# 02_ESP12_CORE.net
KiCad netlist of a schematic drawn in Altium Designer
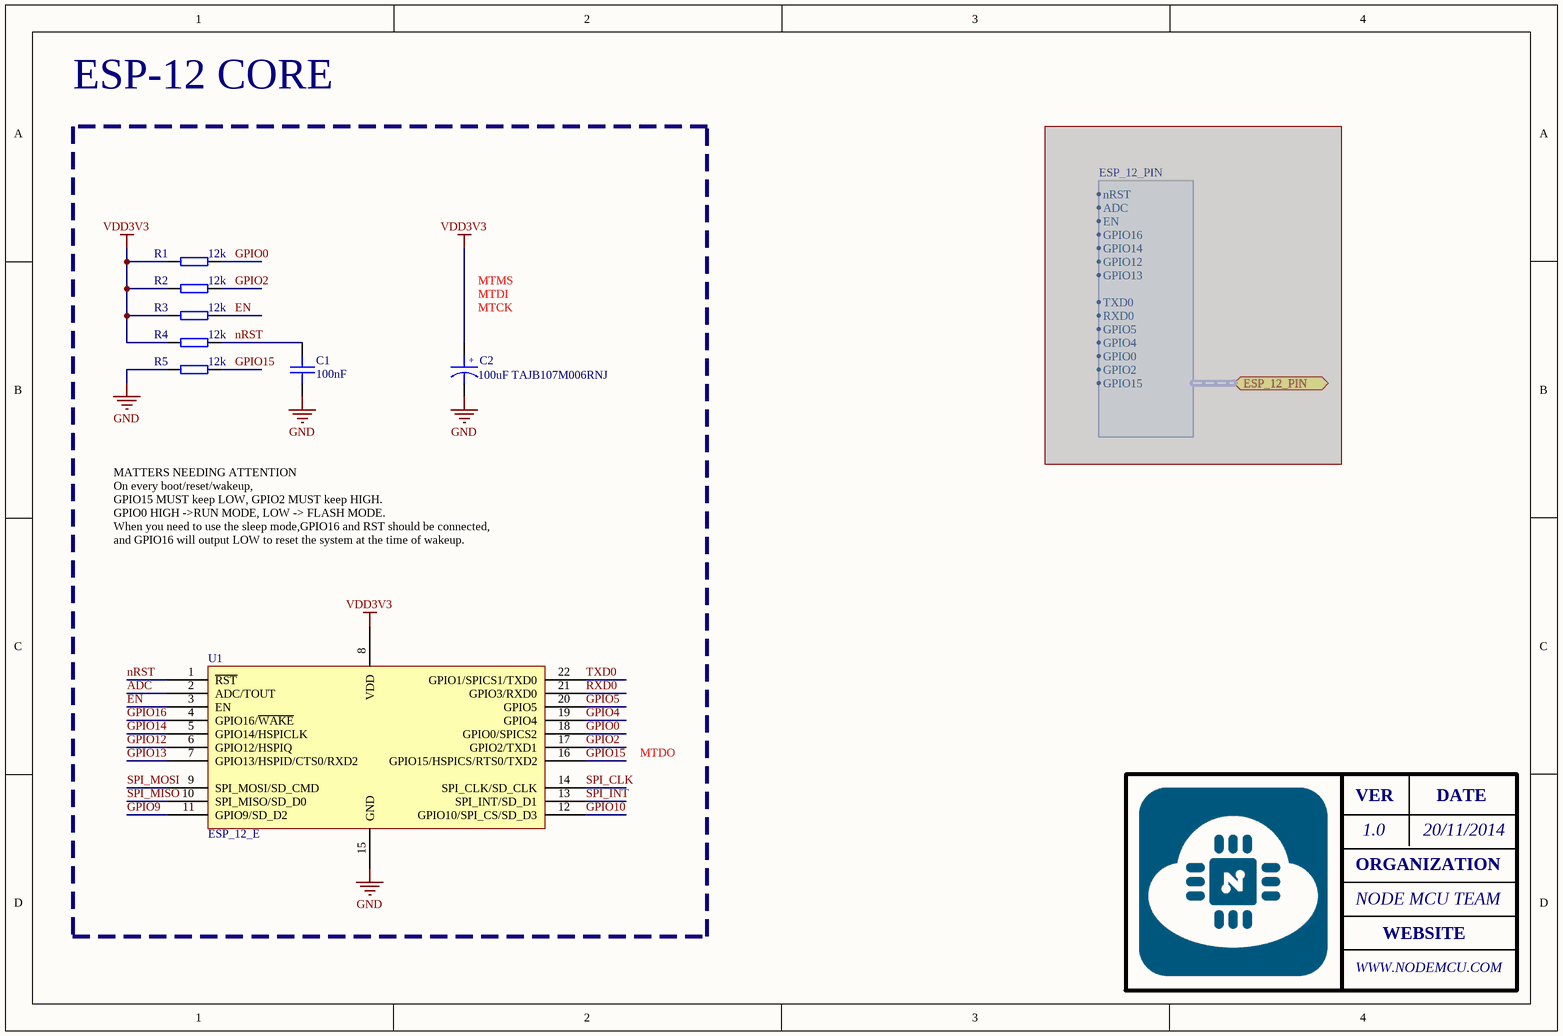
[diagram p0: 02_ESP12_CORE.SchDoc]

(export (version "E")
  (design (tool "Eeschema 10.0.6"))
  (components
    (comp (ref "C1")
      (value "100nF")
      (footprint "SMT_C_0402")
      (description "Surface mount capacitor 0402")
      (libsource (lib "Vowstar_Basic_Device") (part "SMT_C_0402"))
    )
    (comp (ref "C2")
      (value "100uF TAJB107M006RNJ")
      (footprint "SMT_C_Tantalum_B")
      (description "Capacitor, SM Tantalum; Body 3.5 x 2.8 mm (LxW typ)")
      (libsource (lib "Vowstar_Basic_Device") (part "SMT_C_Tantalum_B"))
    )
    (comp (ref "R1")
      (value "12k")
      (footprint "SMT_R_0402")
      (description "Surface mount resistor 0402")
      (libsource (lib "Vowstar_Basic_Device") (part "SMT_R_0402"))
    )
    (comp (ref "R2")
      (value "12k")
      (footprint "SMT_R_0402")
      (description "Surface mount resistor 0402")
      (libsource (lib "Vowstar_Basic_Device") (part "SMT_R_0402"))
    )
    (comp (ref "R3")
      (value "12k")
      (footprint "SMT_R_0402")
      (description "Surface mount resistor 0402")
      (libsource (lib "Vowstar_Basic_Device") (part "SMT_R_0402"))
    )
    (comp (ref "R4")
      (value "12k")
      (footprint "SMT_R_0402")
      (description "Surface mount resistor 0402")
      (libsource (lib "Vowstar_Basic_Device") (part "SMT_R_0402"))
    )
    (comp (ref "R5")
      (value "12k")
      (footprint "SMT_R_0402")
      (description "Surface mount resistor 0402")
      (libsource (lib "Vowstar_Basic_Device") (part "SMT_R_0402"))
    )
    (comp (ref "U1")
      (value "ESP_12_E")
      (footprint "ESP_12_E_L")
      (description "ESP-12 Wi-Fi Module by AI-Thinker")
      (libsource (lib "Vowstar_Module") (part "ESP_12_E"))
    )
  )
  (nets
    (net (code "2") (name "/ADC") (class "Default")
      (node (ref "U1") (pin "2") (pinfunction "ADC/TOUT_2") (pintype "passive"))
    )
    (net (code "3") (name "/EN") (class "Default")
      (node (ref "R3") (pin "2") (pinfunction "2_2") (pintype "passive"))
      (node (ref "U1") (pin "3") (pinfunction "EN_3") (pintype "passive"))
    )
    (net (code "4") (name "/GPIO0") (class "Default")
      (node (ref "R1") (pin "2") (pinfunction "2_2") (pintype "passive"))
      (node (ref "U1") (pin "18") (pinfunction "GPIO0/SPICS2_18") (pintype "passive"))
    )
    (net (code "5") (name "/GPIO2") (class "Default")
      (node (ref "R2") (pin "2") (pinfunction "2_2") (pintype "passive"))
      (node (ref "U1") (pin "17") (pinfunction "GPIO2/TXD1_17") (pintype "passive"))
    )
    (net (code "6") (name "/GPIO4") (class "Default")
      (node (ref "U1") (pin "19") (pinfunction "GPIO4_19") (pintype "passive"))
    )
    (net (code "7") (name "/GPIO5") (class "Default")
      (node (ref "U1") (pin "20") (pinfunction "GPIO5_20") (pintype "passive"))
    )
    (net (code "8") (name "/GPIO9") (class "Default")
      (node (ref "U1") (pin "11") (pinfunction "GPIO9/SD_D2_11") (pintype "passive"))
    )
    (net (code "9") (name "/GPIO10") (class "Default")
      (node (ref "U1") (pin "12") (pinfunction "GPIO10/SPI_CS/SD_D3_12") (pintype "passive"))
    )
    (net (code "10") (name "/GPIO12") (class "Default")
      (node (ref "U1") (pin "6") (pinfunction "GPIO12/HSPIQ_6") (pintype "passive"))
    )
    (net (code "11") (name "/GPIO13") (class "Default")
      (node (ref "U1") (pin "7") (pinfunction "GPIO13/HSPID/CTS0/RXD2_7") (pintype "passive"))
    )
    (net (code "12") (name "/GPIO14") (class "Default")
      (node (ref "U1") (pin "5") (pinfunction "GPIO14/HSPICLK_5") (pintype "passive"))
    )
    (net (code "13") (name "/GPIO15") (class "Default")
      (node (ref "R5") (pin "2") (pinfunction "2_2") (pintype "passive"))
      (node (ref "U1") (pin "16") (pinfunction "GPIO15/HSPICS/RTS0/TXD2_16") (pintype "passive"))
    )
    (net (code "14") (name "/GPIO16") (class "Default")
      (node (ref "U1") (pin "4") (pinfunction "GPIO16/~{WAKE}_4") (pintype "passive"))
    )
    (net (code "15") (name "/RXD0") (class "Default")
      (node (ref "U1") (pin "21") (pinfunction "GPIO3/RXD0_21") (pintype "passive"))
    )
    (net (code "16") (name "/SPI_CLK") (class "Default")
      (node (ref "U1") (pin "14") (pinfunction "SPI_CLK/SD_CLK_14") (pintype "passive"))
    )
    (net (code "17") (name "/SPI_INT") (class "Default")
      (node (ref "U1") (pin "13") (pinfunction "SPI_INT/SD_D1_13") (pintype "passive"))
    )
    (net (code "18") (name "/SPI_MISO") (class "Default")
      (node (ref "U1") (pin "10") (pinfunction "SPI_MISO/SD_D0_10") (pintype "passive"))
    )
    (net (code "19") (name "/SPI_MOSI") (class "Default")
      (node (ref "U1") (pin "9") (pinfunction "SPI_MOSI/SD_CMD_9") (pintype "passive"))
    )
    (net (code "20") (name "/TXD0") (class "Default")
      (node (ref "U1") (pin "22") (pinfunction "GPIO1/SPICS1/TXD0_22") (pintype "passive"))
    )
    (net (code "21") (name "/nRST") (class "Default")
      (node (ref "C1") (pin "1") (pinfunction "1_1") (pintype "passive"))
      (node (ref "R4") (pin "2") (pinfunction "2_2") (pintype "passive"))
      (node (ref "U1") (pin "1") (pinfunction "~{RST}_1") (pintype "passive"))
    )
    (net (code "23") (name "GND") (class "Default")
      (node (ref "C1") (pin "2") (pinfunction "2_2") (pintype "passive"))
      (node (ref "C2") (pin "2") (pinfunction "2_2") (pintype "passive"))
      (node (ref "R5") (pin "1") (pinfunction "1_1") (pintype "passive"))
      (node (ref "U1") (pin "15") (pinfunction "GND_15") (pintype "passive"))
    )
    (net (code "24") (name "VDD3V3") (class "Default")
      (node (ref "C2") (pin "1") (pinfunction "1_1") (pintype "passive"))
      (node (ref "R1") (pin "1") (pinfunction "1_1") (pintype "passive"))
      (node (ref "R2") (pin "1") (pinfunction "1_1") (pintype "passive"))
      (node (ref "R3") (pin "1") (pinfunction "1_1") (pintype "passive"))
      (node (ref "R4") (pin "1") (pinfunction "1_1") (pintype "passive"))
      (node (ref "U1") (pin "8") (pinfunction "VDD_8") (pintype "passive"))
    )
  )
)
